# Tranii.net
KiCad netlist of a schematic drawn in EAGLE
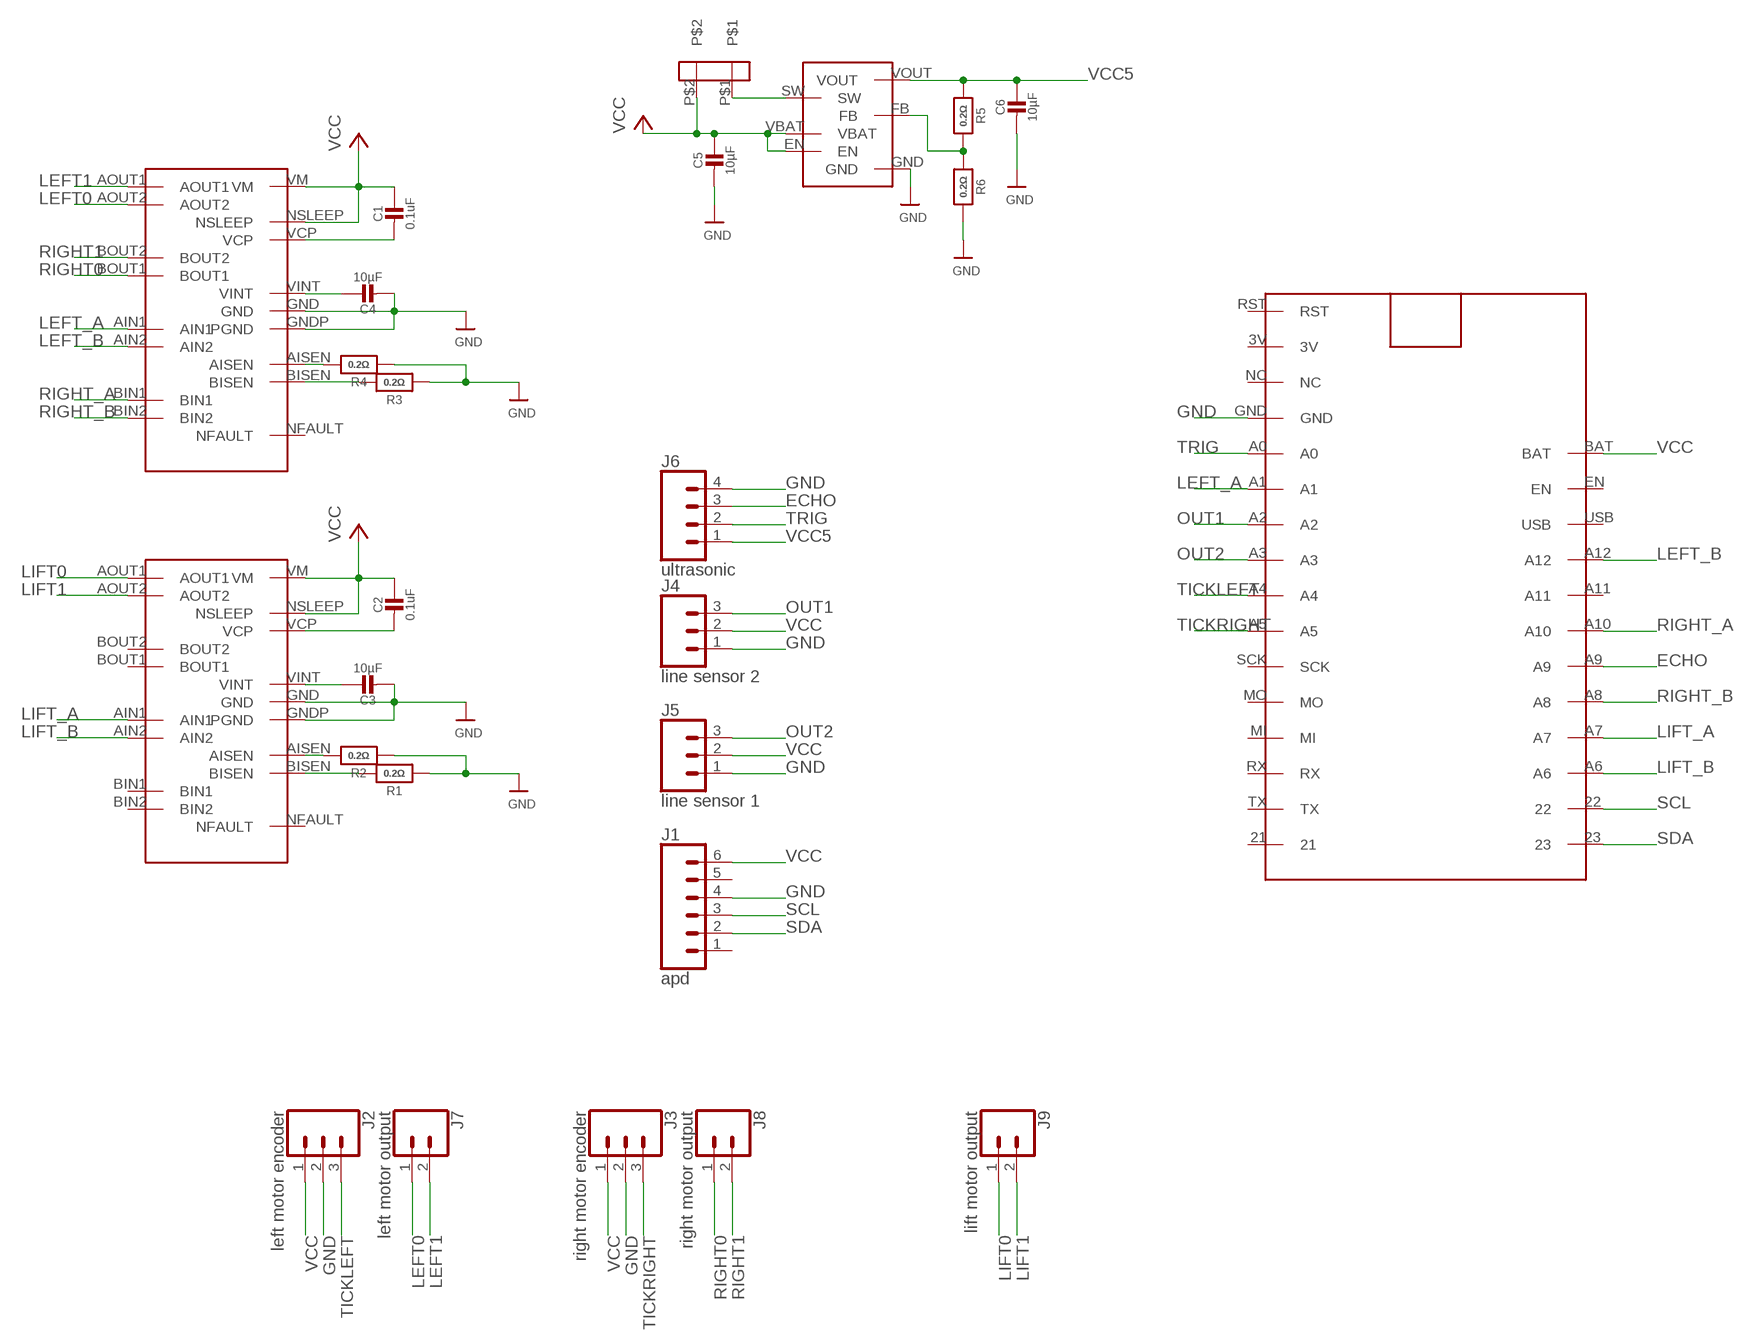
[diagram p0: schematic, sheet 1]

(export (version "E")
  (design (tool "Eeschema 10.0.6"))
  (components
    (comp (ref "C1")
      (value "0.1uF")
      (footprint "eagle-import:0805-NO")
      (libsource (lib "eagle-import") (part "CAP_CERAMIC0805-NOOUTLINE"))
    )
    (comp (ref "C2")
      (value "0.1uF")
      (footprint "eagle-import:0805-NO")
      (libsource (lib "eagle-import") (part "CAP_CERAMIC0805-NOOUTLINE"))
    )
    (comp (ref "C3")
      (value "10µF")
      (footprint "eagle-import:0805-NO")
      (libsource (lib "eagle-import") (part "CAP_CERAMIC0805-NOOUTLINE"))
    )
    (comp (ref "C4")
      (value "10µF")
      (footprint "eagle-import:0805-NO")
      (libsource (lib "eagle-import") (part "CAP_CERAMIC0805-NOOUTLINE"))
    )
    (comp (ref "C5")
      (value "10µF")
      (footprint "eagle-import:0805-NO")
      (libsource (lib "eagle-import") (part "CAP_CERAMIC0805-NOOUTLINE"))
    )
    (comp (ref "C6")
      (value "10µF")
      (footprint "eagle-import:0805-NO")
      (libsource (lib "eagle-import") (part "CAP_CERAMIC0805-NOOUTLINE"))
    )
    (comp (ref "J1")
      (value "apd")
      (footprint "eagle-import:1X06")
      (libsource (lib "eagle-import") (part "CONN_06SILK_FEMALE_PTH"))
    )
    (comp (ref "J2")
      (value "left motor encoder")
      (footprint "eagle-import:1X03")
      (libsource (lib "eagle-import") (part "CONN_03"))
    )
    (comp (ref "J3")
      (value "right motor encoder")
      (footprint "eagle-import:1X03")
      (libsource (lib "eagle-import") (part "CONN_03"))
    )
    (comp (ref "J4")
      (value "line sensor 2")
      (footprint "eagle-import:1X03")
      (libsource (lib "eagle-import") (part "CONN_03"))
    )
    (comp (ref "J5")
      (value "line sensor 1")
      (footprint "eagle-import:1X03")
      (libsource (lib "eagle-import") (part "CONN_03"))
    )
    (comp (ref "J6")
      (value "ultrasonic")
      (footprint "eagle-import:1X04")
      (libsource (lib "eagle-import") (part "CONN_04"))
    )
    (comp (ref "J7")
      (value "left motor output")
      (footprint "eagle-import:1X02")
      (libsource (lib "eagle-import") (part "CONN_02"))
    )
    (comp (ref "J8")
      (value "right motor output")
      (footprint "eagle-import:1X02")
      (libsource (lib "eagle-import") (part "CONN_02"))
    )
    (comp (ref "J9")
      (value "lift motor output")
      (footprint "eagle-import:1X02")
      (libsource (lib "eagle-import") (part "CONN_02"))
    )
    (comp (ref "R1")
      (value "0.2Ω")
      (footprint "eagle-import:_1206")
      (libsource (lib "eagle-import") (part "RESISTOR_1206"))
    )
    (comp (ref "R2")
      (value "0.2Ω")
      (footprint "eagle-import:_1206")
      (libsource (lib "eagle-import") (part "RESISTOR_1206"))
    )
    (comp (ref "R3")
      (value "0.2Ω")
      (footprint "eagle-import:_1206")
      (libsource (lib "eagle-import") (part "RESISTOR_1206"))
    )
    (comp (ref "R4")
      (value "0.2Ω")
      (footprint "eagle-import:_1206")
      (libsource (lib "eagle-import") (part "RESISTOR_1206"))
    )
    (comp (ref "R5")
      (value "0.2Ω")
      (footprint "eagle-import:_1206")
      (libsource (lib "eagle-import") (part "RESISTOR_1206"))
    )
    (comp (ref "R6")
      (value "0.2Ω")
      (footprint "eagle-import:_1206")
      (libsource (lib "eagle-import") (part "RESISTOR_1206"))
    )
    (comp (ref "U$1")
      (value "DRV8833")
      (footprint "eagle-import:DRV8833")
      (libsource (lib "eagle-import") (part "DRV8833"))
    )
    (comp (ref "U$2")
      (value "DRV8833")
      (footprint "eagle-import:DRV8833")
      (libsource (lib "eagle-import") (part "DRV8833"))
    )
    (comp (ref "U$6")
      (value "ESP32")
      (footprint "eagle-import:ESP32")
      (libsource (lib "eagle-import") (part "ESP32"))
    )
    (comp (ref "U$8")
      (value "LPV61220")
      (footprint "eagle-import:TLV61220")
      (libsource (lib "eagle-import") (part "LPV61220"))
    )
    (comp (ref "U$11")
      (value "VLS3012HBX")
      (footprint "eagle-import:VLS3012HBX")
      (libsource (lib "eagle-import") (part "VLS3012HBX"))
    )
  )
  (nets
    (net (code "1") (name "/ECHO") (class "Default")
      (node (ref "J6") (pin "3") (pinfunction "3_3") (pintype "passive"))
      (node (ref "U$6") (pin "A9") (pinfunction "A9_A9") (pintype "bidirectional"))
    )
    (net (code "2") (name "/LEFT0") (class "Default")
      (node (ref "J7") (pin "1") (pinfunction "1_1") (pintype "passive"))
      (node (ref "U$1") (pin "AOUT2") (pinfunction "AOUT2_AOUT2") (pintype "bidirectional"))
    )
    (net (code "3") (name "/LEFT1") (class "Default")
      (node (ref "J7") (pin "2") (pinfunction "2_2") (pintype "passive"))
      (node (ref "U$1") (pin "AOUT1") (pinfunction "AOUT1_AOUT1") (pintype "bidirectional"))
    )
    (net (code "4") (name "/LEFT_A") (class "Default")
      (node (ref "U$1") (pin "AIN1") (pinfunction "AIN1_AIN1") (pintype "bidirectional"))
      (node (ref "U$6") (pin "A1") (pinfunction "A1_A1") (pintype "bidirectional"))
    )
    (net (code "5") (name "/LEFT_B") (class "Default")
      (node (ref "U$1") (pin "AIN2") (pinfunction "AIN2_AIN2") (pintype "bidirectional"))
      (node (ref "U$6") (pin "A12") (pinfunction "A12_A12") (pintype "bidirectional"))
    )
    (net (code "6") (name "/LIFT0") (class "Default")
      (node (ref "J9") (pin "1") (pinfunction "1_1") (pintype "passive"))
      (node (ref "U$2") (pin "AOUT1") (pinfunction "AOUT1_AOUT1") (pintype "bidirectional"))
    )
    (net (code "7") (name "/LIFT1") (class "Default")
      (node (ref "J9") (pin "2") (pinfunction "2_2") (pintype "passive"))
      (node (ref "U$2") (pin "AOUT2") (pinfunction "AOUT2_AOUT2") (pintype "bidirectional"))
    )
    (net (code "8") (name "/LIFT_A") (class "Default")
      (node (ref "U$2") (pin "AIN1") (pinfunction "AIN1_AIN1") (pintype "bidirectional"))
      (node (ref "U$6") (pin "A7") (pinfunction "A7_A7") (pintype "bidirectional"))
    )
    (net (code "9") (name "/LIFT_B") (class "Default")
      (node (ref "U$2") (pin "AIN2") (pinfunction "AIN2_AIN2") (pintype "bidirectional"))
      (node (ref "U$6") (pin "A6") (pinfunction "A6_A6") (pintype "bidirectional"))
    )
    (net (code "10") (name "/OUT1") (class "Default")
      (node (ref "J4") (pin "3") (pinfunction "3_3") (pintype "passive"))
      (node (ref "U$6") (pin "A2") (pinfunction "A2_A2") (pintype "bidirectional"))
    )
    (net (code "11") (name "/OUT2") (class "Default")
      (node (ref "J5") (pin "3") (pinfunction "3_3") (pintype "passive"))
      (node (ref "U$6") (pin "A3") (pinfunction "A3_A3") (pintype "bidirectional"))
    )
    (net (code "12") (name "/RIGHT0") (class "Default")
      (node (ref "J8") (pin "1") (pinfunction "1_1") (pintype "passive"))
      (node (ref "U$1") (pin "BOUT1") (pinfunction "BOUT1_BOUT1") (pintype "bidirectional"))
    )
    (net (code "13") (name "/RIGHT1") (class "Default")
      (node (ref "J8") (pin "2") (pinfunction "2_2") (pintype "passive"))
      (node (ref "U$1") (pin "BOUT2") (pinfunction "BOUT2_BOUT2") (pintype "bidirectional"))
    )
    (net (code "14") (name "/RIGHT_A") (class "Default")
      (node (ref "U$1") (pin "BIN1") (pinfunction "BIN1_BIN1") (pintype "bidirectional"))
      (node (ref "U$6") (pin "A10") (pinfunction "A10_A10") (pintype "bidirectional"))
    )
    (net (code "15") (name "/RIGHT_B") (class "Default")
      (node (ref "U$1") (pin "BIN2") (pinfunction "BIN2_BIN2") (pintype "bidirectional"))
      (node (ref "U$6") (pin "A8") (pinfunction "A8_A8") (pintype "bidirectional"))
    )
    (net (code "16") (name "/SCL") (class "Default")
      (node (ref "J1") (pin "3") (pinfunction "3_3") (pintype "passive"))
      (node (ref "U$6") (pin "22") (pinfunction "22_22") (pintype "bidirectional"))
    )
    (net (code "17") (name "/SDA") (class "Default")
      (node (ref "J1") (pin "2") (pinfunction "2_2") (pintype "passive"))
      (node (ref "U$6") (pin "23") (pinfunction "23_23") (pintype "bidirectional"))
    )
    (net (code "18") (name "/TICKLEFT") (class "Default")
      (node (ref "J2") (pin "3") (pinfunction "3_3") (pintype "passive"))
      (node (ref "U$6") (pin "A4") (pinfunction "A4_A4") (pintype "bidirectional"))
    )
    (net (code "19") (name "/TICKRIGHT") (class "Default")
      (node (ref "J3") (pin "3") (pinfunction "3_3") (pintype "passive"))
      (node (ref "U$6") (pin "A5") (pinfunction "A5_A5") (pintype "bidirectional"))
    )
    (net (code "20") (name "/TRIG") (class "Default")
      (node (ref "J6") (pin "2") (pinfunction "2_2") (pintype "passive"))
      (node (ref "U$6") (pin "A0") (pinfunction "A0_A0") (pintype "bidirectional"))
    )
    (net (code "21") (name "/VCC5") (class "Default")
      (node (ref "C6") (pin "1") (pinfunction "1_1") (pintype "passive"))
      (node (ref "J6") (pin "1") (pinfunction "1_1") (pintype "passive"))
      (node (ref "R5") (pin "1") (pinfunction "1_1") (pintype "passive"))
      (node (ref "U$8") (pin "VOUT") (pinfunction "VOUT_VOUT") (pintype "bidirectional"))
    )
    (net (code "22") (name "GND") (class "Default")
      (node (ref "C3") (pin "2") (pinfunction "2_2") (pintype "passive"))
      (node (ref "C4") (pin "2") (pinfunction "2_2") (pintype "passive"))
      (node (ref "C5") (pin "2") (pinfunction "2_2") (pintype "passive"))
      (node (ref "C6") (pin "2") (pinfunction "2_2") (pintype "passive"))
      (node (ref "J1") (pin "4") (pinfunction "4_4") (pintype "passive"))
      (node (ref "J2") (pin "2") (pinfunction "2_2") (pintype "passive"))
      (node (ref "J3") (pin "2") (pinfunction "2_2") (pintype "passive"))
      (node (ref "J4") (pin "1") (pinfunction "1_1") (pintype "passive"))
      (node (ref "J5") (pin "1") (pinfunction "1_1") (pintype "passive"))
      (node (ref "J6") (pin "4") (pinfunction "4_4") (pintype "passive"))
      (node (ref "R1") (pin "1") (pinfunction "1_1") (pintype "passive"))
      (node (ref "R2") (pin "1") (pinfunction "1_1") (pintype "passive"))
      (node (ref "R3") (pin "1") (pinfunction "1_1") (pintype "passive"))
      (node (ref "R4") (pin "1") (pinfunction "1_1") (pintype "passive"))
      (node (ref "R6") (pin "2") (pinfunction "2_2") (pintype "passive"))
      (node (ref "U$1") (pin "GND") (pinfunction "GND_GND") (pintype "bidirectional"))
      (node (ref "U$1") (pin "GNDP") (pinfunction "PGND_GNDP") (pintype "bidirectional"))
      (node (ref "U$2") (pin "GND") (pinfunction "GND_GND") (pintype "bidirectional"))
      (node (ref "U$2") (pin "GNDP") (pinfunction "PGND_GNDP") (pintype "bidirectional"))
      (node (ref "U$6") (pin "GND") (pinfunction "GND_GND") (pintype "bidirectional"))
      (node (ref "U$8") (pin "GND") (pinfunction "GND_GND") (pintype "bidirectional"))
    )
    (net (code "23") (name "Net-(C1-Pad2)") (class "Default")
      (node (ref "C1") (pin "2") (pinfunction "2_2") (pintype "passive"))
      (node (ref "U$1") (pin "VCP") (pinfunction "VCP_VCP") (pintype "bidirectional"))
    )
    (net (code "24") (name "Net-(C2-Pad2)") (class "Default")
      (node (ref "C2") (pin "2") (pinfunction "2_2") (pintype "passive"))
      (node (ref "U$2") (pin "VCP") (pinfunction "VCP_VCP") (pintype "bidirectional"))
    )
    (net (code "25") (name "Net-(C3-Pad1)") (class "Default")
      (node (ref "C3") (pin "1") (pinfunction "1_1") (pintype "passive"))
      (node (ref "U$2") (pin "VINT") (pinfunction "VINT_VINT") (pintype "bidirectional"))
    )
    (net (code "26") (name "Net-(C4-Pad1)") (class "Default")
      (node (ref "C4") (pin "1") (pinfunction "1_1") (pintype "passive"))
      (node (ref "U$1") (pin "VINT") (pinfunction "VINT_VINT") (pintype "bidirectional"))
    )
    (net (code "27") (name "Net-(R1-Pad2)") (class "Default")
      (node (ref "R1") (pin "2") (pinfunction "2_2") (pintype "passive"))
      (node (ref "U$2") (pin "BISEN") (pinfunction "BISEN_BISEN") (pintype "bidirectional"))
    )
    (net (code "28") (name "Net-(R2-Pad2)") (class "Default")
      (node (ref "R2") (pin "2") (pinfunction "2_2") (pintype "passive"))
      (node (ref "U$2") (pin "AISEN") (pinfunction "AISEN_AISEN") (pintype "bidirectional"))
    )
    (net (code "29") (name "Net-(R3-Pad2)") (class "Default")
      (node (ref "R3") (pin "2") (pinfunction "2_2") (pintype "passive"))
      (node (ref "U$1") (pin "BISEN") (pinfunction "BISEN_BISEN") (pintype "bidirectional"))
    )
    (net (code "30") (name "Net-(R4-Pad2)") (class "Default")
      (node (ref "R4") (pin "2") (pinfunction "2_2") (pintype "passive"))
      (node (ref "U$1") (pin "AISEN") (pinfunction "AISEN_AISEN") (pintype "bidirectional"))
    )
    (net (code "31") (name "Net-(R5-Pad2)") (class "Default")
      (node (ref "R5") (pin "2") (pinfunction "2_2") (pintype "passive"))
      (node (ref "R6") (pin "1") (pinfunction "1_1") (pintype "passive"))
      (node (ref "U$8") (pin "FB") (pinfunction "FB_FB") (pintype "bidirectional"))
    )
    (net (code "32") (name "Net-(U$11-PadP$1)") (class "Default")
      (node (ref "U$11") (pin "P$1") (pinfunction "P$1_P$1") (pintype "bidirectional"))
      (node (ref "U$8") (pin "SW") (pinfunction "SW_SW") (pintype "bidirectional"))
    )
    (net (code "33") (name "VCC") (class "Default")
      (node (ref "C1") (pin "1") (pinfunction "1_1") (pintype "passive"))
      (node (ref "C2") (pin "1") (pinfunction "1_1") (pintype "passive"))
      (node (ref "C5") (pin "1") (pinfunction "1_1") (pintype "passive"))
      (node (ref "J1") (pin "6") (pinfunction "6_6") (pintype "passive"))
      (node (ref "J2") (pin "1") (pinfunction "1_1") (pintype "passive"))
      (node (ref "J3") (pin "1") (pinfunction "1_1") (pintype "passive"))
      (node (ref "J4") (pin "2") (pinfunction "2_2") (pintype "passive"))
      (node (ref "J5") (pin "2") (pinfunction "2_2") (pintype "passive"))
      (node (ref "U$1") (pin "NSLEEP") (pinfunction "NSLEEP_NSLEEP") (pintype "bidirectional"))
      (node (ref "U$1") (pin "VM") (pinfunction "VM_VM") (pintype "bidirectional"))
      (node (ref "U$11") (pin "P$2") (pinfunction "P$2_P$2") (pintype "bidirectional"))
      (node (ref "U$2") (pin "NSLEEP") (pinfunction "NSLEEP_NSLEEP") (pintype "bidirectional"))
      (node (ref "U$2") (pin "VM") (pinfunction "VM_VM") (pintype "bidirectional"))
      (node (ref "U$6") (pin "BAT") (pinfunction "BAT_BAT") (pintype "bidirectional"))
      (node (ref "U$8") (pin "EN") (pinfunction "EN_EN") (pintype "bidirectional"))
      (node (ref "U$8") (pin "VBAT") (pinfunction "VBAT_VBAT") (pintype "bidirectional"))
    )
    (net (code "34") (name "unconnected-(J1-Pad1)") (class "Default")
      (node (ref "J1") (pin "1") (pinfunction "1_1") (pintype "passive"))
    )
    (net (code "35") (name "unconnected-(J1-Pad5)") (class "Default")
      (node (ref "J1") (pin "5") (pinfunction "5_5") (pintype "passive"))
    )
    (net (code "36") (name "unconnected-(U$1-PadNFAULT)") (class "Default")
      (node (ref "U$1") (pin "NFAULT") (pinfunction "NFAULT_NFAULT") (pintype "bidirectional"))
    )
    (net (code "37") (name "unconnected-(U$2-PadBIN1)") (class "Default")
      (node (ref "U$2") (pin "BIN1") (pinfunction "BIN1_BIN1") (pintype "bidirectional"))
    )
    (net (code "38") (name "unconnected-(U$2-PadBIN2)") (class "Default")
      (node (ref "U$2") (pin "BIN2") (pinfunction "BIN2_BIN2") (pintype "bidirectional"))
    )
    (net (code "39") (name "unconnected-(U$2-PadBOUT1)") (class "Default")
      (node (ref "U$2") (pin "BOUT1") (pinfunction "BOUT1_BOUT1") (pintype "bidirectional"))
    )
    (net (code "40") (name "unconnected-(U$2-PadBOUT2)") (class "Default")
      (node (ref "U$2") (pin "BOUT2") (pinfunction "BOUT2_BOUT2") (pintype "bidirectional"))
    )
    (net (code "41") (name "unconnected-(U$2-PadNFAULT)") (class "Default")
      (node (ref "U$2") (pin "NFAULT") (pinfunction "NFAULT_NFAULT") (pintype "bidirectional"))
    )
    (net (code "42") (name "unconnected-(U$6-Pad3V)") (class "Default")
      (node (ref "U$6") (pin "3V") (pinfunction "3V_3V") (pintype "bidirectional"))
    )
    (net (code "43") (name "unconnected-(U$6-Pad21)") (class "Default")
      (node (ref "U$6") (pin "21") (pinfunction "21_21") (pintype "bidirectional"))
    )
    (net (code "44") (name "unconnected-(U$6-PadA11)") (class "Default")
      (node (ref "U$6") (pin "A11") (pinfunction "A11_A11") (pintype "bidirectional"))
    )
    (net (code "45") (name "unconnected-(U$6-PadEN)") (class "Default")
      (node (ref "U$6") (pin "EN") (pinfunction "EN_EN") (pintype "bidirectional"))
    )
    (net (code "46") (name "unconnected-(U$6-PadMI)") (class "Default")
      (node (ref "U$6") (pin "MI") (pinfunction "MI_MI") (pintype "bidirectional"))
    )
    (net (code "47") (name "unconnected-(U$6-PadMO)") (class "Default")
      (node (ref "U$6") (pin "MO") (pinfunction "MO_MO") (pintype "bidirectional"))
    )
    (net (code "48") (name "unconnected-(U$6-PadNC)") (class "Default")
      (node (ref "U$6") (pin "NC") (pinfunction "NC_NC") (pintype "bidirectional"))
    )
    (net (code "49") (name "unconnected-(U$6-PadRST)") (class "Default")
      (node (ref "U$6") (pin "RST") (pinfunction "RST_RST") (pintype "bidirectional"))
    )
    (net (code "50") (name "unconnected-(U$6-PadRX)") (class "Default")
      (node (ref "U$6") (pin "RX") (pinfunction "RX_RX") (pintype "bidirectional"))
    )
    (net (code "51") (name "unconnected-(U$6-PadSCK)") (class "Default")
      (node (ref "U$6") (pin "SCK") (pinfunction "SCK_SCK") (pintype "bidirectional"))
    )
    (net (code "52") (name "unconnected-(U$6-PadTX)") (class "Default")
      (node (ref "U$6") (pin "TX") (pinfunction "TX_TX") (pintype "bidirectional"))
    )
    (net (code "53") (name "unconnected-(U$6-PadUSB)") (class "Default")
      (node (ref "U$6") (pin "USB") (pinfunction "USB_USB") (pintype "bidirectional"))
    )
  )
)
